# StmPulse-V2-inprogress.net
KiCad netlist of a schematic drawn in EAGLE
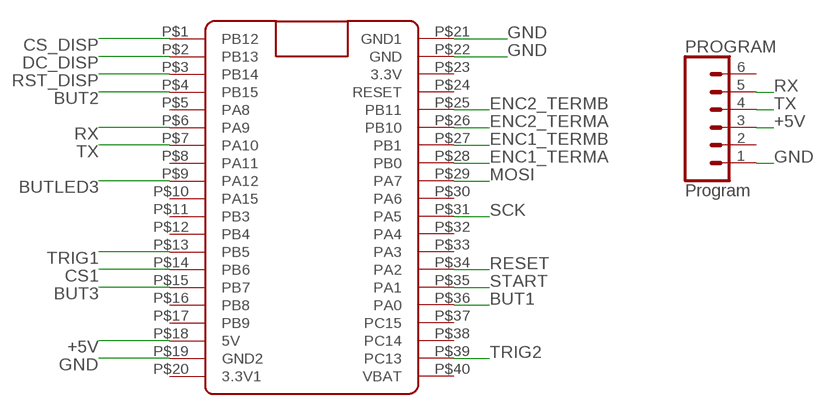
[diagram p0: schematic, sheet 1]
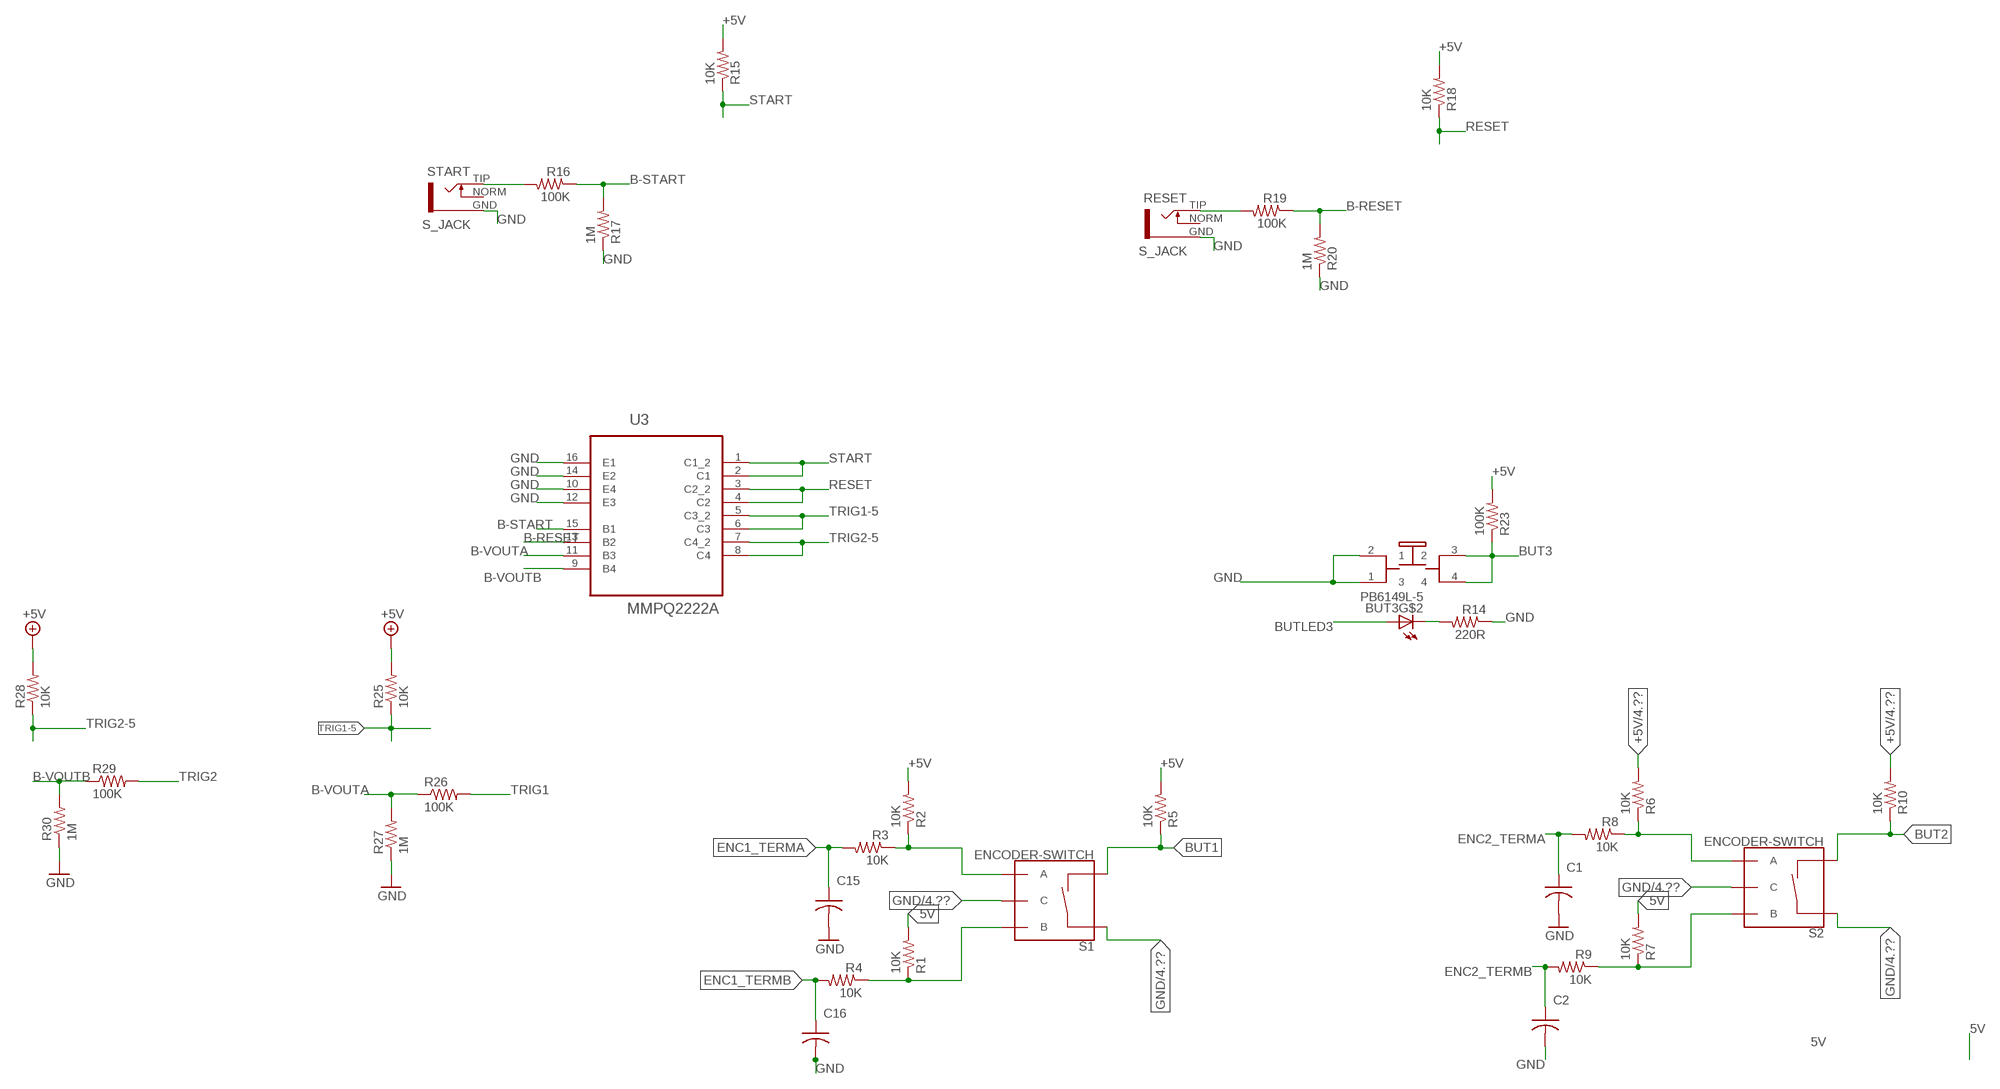
[diagram p1: schematic, sheet 2]
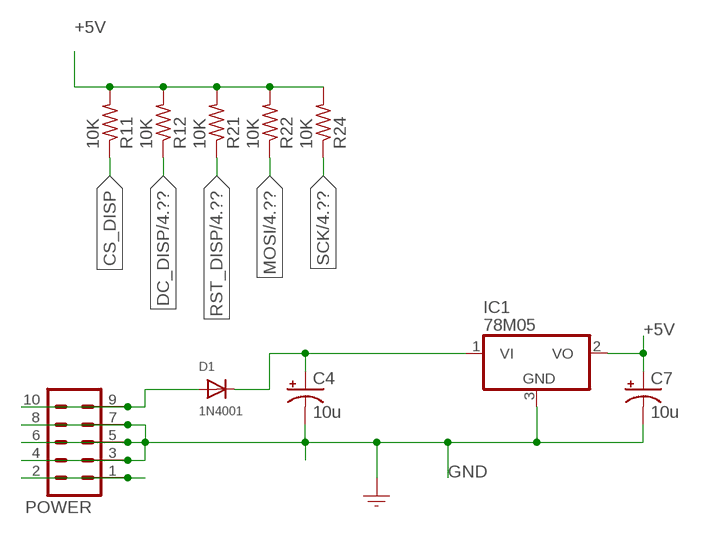
[diagram p2: schematic, sheet 3]
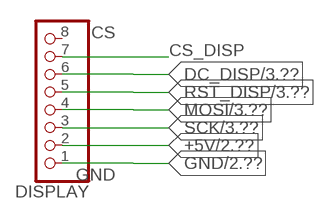
[diagram p3: schematic, sheet 4]
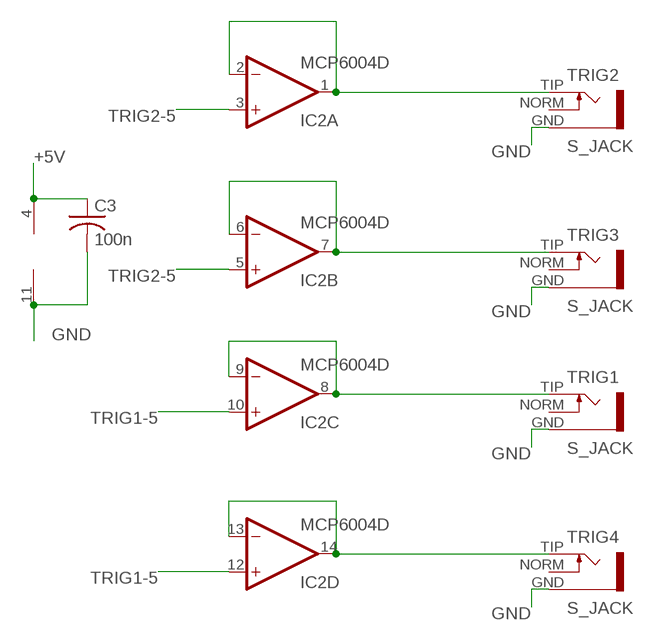
[diagram p4: schematic, sheet 5]
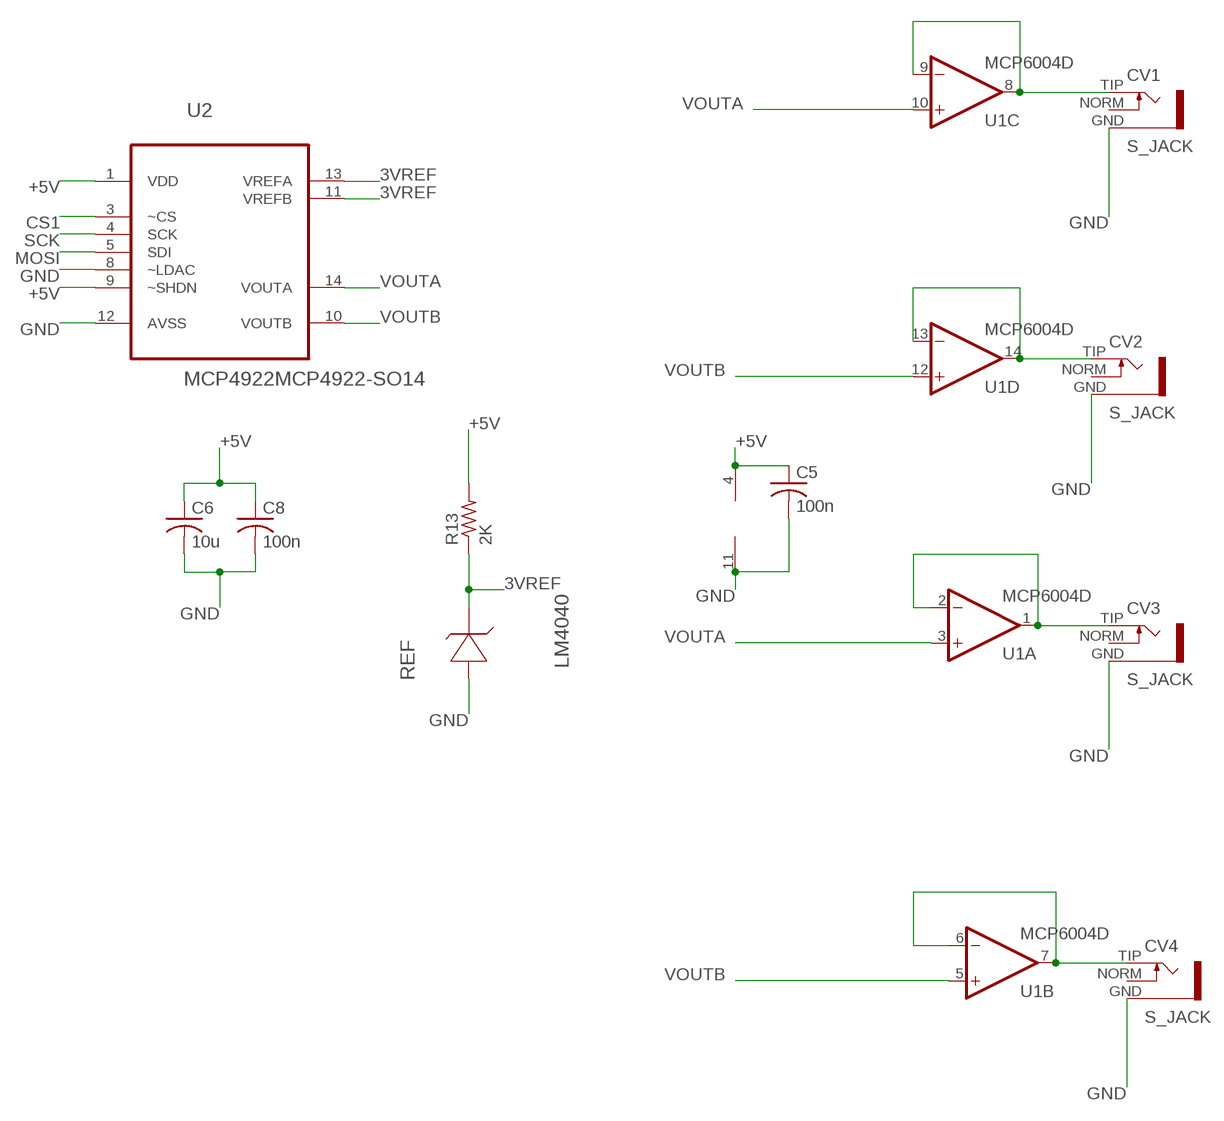
[diagram p5: schematic, sheet 6]

(export (version "E")
  (design (tool "Eeschema 10.0.6"))
  (components
    (comp (ref "BUT3")
      (value "PB6149L-5")
      (footprint "eagle-import:PB6149L")
      (libsource (lib "eagle-import") (part "PB6149L-5"))
    )
    (comp (ref "C1")
      (value "10nF")
      (footprint "eagle-import:C0805")
      (libsource (lib "eagle-import") (part "C-USC0805"))
    )
    (comp (ref "C2")
      (value "10nF")
      (footprint "eagle-import:C0805")
      (libsource (lib "eagle-import") (part "C-USC0805"))
    )
    (comp (ref "C15")
      (value "10nF")
      (footprint "eagle-import:C0805")
      (libsource (lib "eagle-import") (part "C-USC0805"))
    )
    (comp (ref "C16")
      (value "10nF")
      (footprint "eagle-import:C0805")
      (libsource (lib "eagle-import") (part "C-USC0805"))
    )
    (comp (ref "R1")
      (value "10K")
      (footprint "eagle-import:R0805")
      (libsource (lib "eagle-import") (part "R-US_R0805"))
    )
    (comp (ref "R2")
      (value "10K")
      (footprint "eagle-import:R0805")
      (libsource (lib "eagle-import") (part "R-US_R0805"))
    )
    (comp (ref "R3")
      (value "10K")
      (footprint "eagle-import:R0805")
      (libsource (lib "eagle-import") (part "R-US_R0805"))
    )
    (comp (ref "R4")
      (value "10K")
      (footprint "eagle-import:R0805")
      (libsource (lib "eagle-import") (part "R-US_R0805"))
    )
    (comp (ref "R5")
      (value "10K")
      (footprint "eagle-import:R0805")
      (libsource (lib "eagle-import") (part "R-US_R0805"))
    )
    (comp (ref "R6")
      (value "10K")
      (footprint "eagle-import:R0805")
      (libsource (lib "eagle-import") (part "R-US_R0805"))
    )
    (comp (ref "R7")
      (value "10K")
      (footprint "eagle-import:R0805")
      (libsource (lib "eagle-import") (part "R-US_R0805"))
    )
    (comp (ref "R8")
      (value "10K")
      (footprint "eagle-import:R0805")
      (libsource (lib "eagle-import") (part "R-US_R0805"))
    )
    (comp (ref "R9")
      (value "10K")
      (footprint "eagle-import:R0805")
      (libsource (lib "eagle-import") (part "R-US_R0805"))
    )
    (comp (ref "R10")
      (value "10K")
      (footprint "eagle-import:R0805")
      (libsource (lib "eagle-import") (part "R-US_R0805"))
    )
    (comp (ref "R14")
      (value "220R")
      (footprint "eagle-import:R0805")
      (libsource (lib "eagle-import") (part "R-US_R0805"))
    )
    (comp (ref "R15")
      (value "10K")
      (footprint "eagle-import:R0805")
      (libsource (lib "eagle-import") (part "R-US_R0805"))
    )
    (comp (ref "R16")
      (value "100K")
      (footprint "eagle-import:R0805")
      (libsource (lib "eagle-import") (part "R-US_R0805"))
    )
    (comp (ref "R17")
      (value "1M")
      (footprint "eagle-import:R0805")
      (libsource (lib "eagle-import") (part "R-US_R0805"))
    )
    (comp (ref "R18")
      (value "10K")
      (footprint "eagle-import:R0805")
      (libsource (lib "eagle-import") (part "R-US_R0805"))
    )
    (comp (ref "R19")
      (value "100K")
      (footprint "eagle-import:R0805")
      (libsource (lib "eagle-import") (part "R-US_R0805"))
    )
    (comp (ref "R20")
      (value "1M")
      (footprint "eagle-import:R0805")
      (libsource (lib "eagle-import") (part "R-US_R0805"))
    )
    (comp (ref "R23")
      (value "100K")
      (footprint "eagle-import:R0805")
      (libsource (lib "eagle-import") (part "R-US_R0805"))
    )
    (comp (ref "R25")
      (value "10K")
      (footprint "eagle-import:R0805")
      (libsource (lib "eagle-import") (part "R-US_R0805"))
    )
    (comp (ref "R26")
      (value "100K")
      (footprint "eagle-import:R0805")
      (libsource (lib "eagle-import") (part "R-US_R0805"))
    )
    (comp (ref "R27")
      (value "1M")
      (footprint "eagle-import:R0805")
      (libsource (lib "eagle-import") (part "R-US_R0805"))
    )
    (comp (ref "R28")
      (value "10K")
      (footprint "eagle-import:R0805")
      (libsource (lib "eagle-import") (part "R-US_R0805"))
    )
    (comp (ref "R29")
      (value "100K")
      (footprint "eagle-import:R0805")
      (libsource (lib "eagle-import") (part "R-US_R0805"))
    )
    (comp (ref "R30")
      (value "1M")
      (footprint "eagle-import:R0805")
      (libsource (lib "eagle-import") (part "R-US_R0805"))
    )
    (comp (ref "RESET")
      (value "S_JACK")
      (footprint "eagle-import:S_JACK")
      (libsource (lib "eagle-import") (part "S_JACK"))
    )
    (comp (ref "S1")
      (value "ENCODER-SWITCH")
      (footprint "eagle-import:ROTARY_ENC_PLAIN")
      (libsource (lib "eagle-import") (part "ENCODER-SWITCH"))
    )
    (comp (ref "S2")
      (value "ENCODER-SWITCH")
      (footprint "eagle-import:ROTARY_ENC_PLAIN")
      (libsource (lib "eagle-import") (part "ENCODER-SWITCH"))
    )
    (comp (ref "START")
      (value "S_JACK")
      (footprint "eagle-import:S_JACK")
      (libsource (lib "eagle-import") (part "S_JACK"))
    )
    (comp (ref "U3")
      (value "MMPQ2222A")
      (footprint "eagle-import:SOIC127P600X175-16N")
      (libsource (lib "eagle-import") (part "MMPQ2222A"))
    )
    (comp (ref "DISPLAY")
      (value "MICROBUILDER_HEADER-1X8ROUND")
      (footprint "eagle-import:MICROBUILDER_1X08_ROUND")
      (libsource (lib "eagle-import") (part "MICROBUILDER_HEADER-1X8ROUND"))
    )
    (comp (ref "PROGRAM")
      (value "Program")
      (footprint "eagle-import:1X06")
      (libsource (lib "eagle-import") (part "CONN_06SILK_FEMALE_PTH"))
    )
    (comp (ref "U$1")
      (value "Blue Pill")
      (footprint "eagle-import:BLUE_PILL")
      (libsource (lib "eagle-import") (part "BLUE_PILL"))
    )
    (comp (ref "C3")
      (value "100n")
      (footprint "eagle-import:C0805K")
      (libsource (lib "eagle-import") (part "C-USC0805K"))
    )
    (comp (ref "IC2")
      (value "MCP6004D")
      (footprint "eagle-import:SO14")
      (libsource (lib "eagle-import") (part "MCP6004D"))
    )
    (comp (ref "TRIG1")
      (value "S_JACK")
      (footprint "eagle-import:S_JACK")
      (libsource (lib "eagle-import") (part "S_JACK"))
    )
    (comp (ref "TRIG2")
      (value "S_JACK")
      (footprint "eagle-import:S_JACK")
      (libsource (lib "eagle-import") (part "S_JACK"))
    )
    (comp (ref "TRIG3")
      (value "S_JACK")
      (footprint "eagle-import:S_JACK")
      (libsource (lib "eagle-import") (part "S_JACK"))
    )
    (comp (ref "TRIG4")
      (value "S_JACK")
      (footprint "eagle-import:S_JACK")
      (libsource (lib "eagle-import") (part "S_JACK"))
    )
    (comp (ref "C4")
      (value "10u")
      (footprint "eagle-import:153CLV-0505")
      (libsource (lib "eagle-import") (part "CAPACITOR_POL-US153CLV-0505"))
    )
    (comp (ref "C7")
      (value "10u")
      (footprint "eagle-import:153CLV-0505")
      (libsource (lib "eagle-import") (part "CAPACITOR_POL-US153CLV-0505"))
    )
    (comp (ref "D1")
      (value "1N4001")
      (footprint "eagle-import:SMADIODE")
      (libsource (lib "eagle-import") (part "DIODESMA"))
    )
    (comp (ref "IC1")
      (value "78M05")
      (footprint "eagle-import:TO252")
      (libsource (lib "eagle-import") (part "VOLTAGE_REG_POSDT05"))
    )
    (comp (ref "POWER")
      (value "CONN_05X2SHD_SMD")
      (footprint "eagle-import:2X5-SHROUDED_SMD")
      (fields (field (name "RS-PART") "828-1783"))
      (libsource (lib "eagle-import") (part "CONN_05X2SHD_SMD"))
    )
    (comp (ref "R11")
      (value "10K")
      (footprint "eagle-import:R0805")
      (libsource (lib "eagle-import") (part "R-US_R0805"))
    )
    (comp (ref "R12")
      (value "10K")
      (footprint "eagle-import:R0805")
      (libsource (lib "eagle-import") (part "R-US_R0805"))
    )
    (comp (ref "R21")
      (value "10K")
      (footprint "eagle-import:R0805")
      (libsource (lib "eagle-import") (part "R-US_R0805"))
    )
    (comp (ref "R22")
      (value "10K")
      (footprint "eagle-import:R0805")
      (libsource (lib "eagle-import") (part "R-US_R0805"))
    )
    (comp (ref "R24")
      (value "10K")
      (footprint "eagle-import:R0805")
      (libsource (lib "eagle-import") (part "R-US_R0805"))
    )
    (comp (ref "C5")
      (value "100n")
      (footprint "eagle-import:C0805K")
      (libsource (lib "eagle-import") (part "C-USC0805K"))
    )
    (comp (ref "C6")
      (value "10u")
      (footprint "eagle-import:C0805K")
      (libsource (lib "eagle-import") (part "C-USC0805K"))
    )
    (comp (ref "C8")
      (value "100n")
      (footprint "eagle-import:C0805K")
      (libsource (lib "eagle-import") (part "C-USC0805K"))
    )
    (comp (ref "CV1")
      (value "S_JACK")
      (footprint "eagle-import:S_JACK")
      (libsource (lib "eagle-import") (part "S_JACK"))
    )
    (comp (ref "CV2")
      (value "S_JACK")
      (footprint "eagle-import:S_JACK")
      (libsource (lib "eagle-import") (part "S_JACK"))
    )
    (comp (ref "CV3")
      (value "S_JACK")
      (footprint "eagle-import:S_JACK")
      (libsource (lib "eagle-import") (part "S_JACK"))
    )
    (comp (ref "CV4")
      (value "S_JACK")
      (footprint "eagle-import:S_JACK")
      (libsource (lib "eagle-import") (part "S_JACK"))
    )
    (comp (ref "R13")
      (value "2K")
      (footprint "eagle-import:R0805")
      (libsource (lib "eagle-import") (part "R-US_R0805"))
    )
    (comp (ref "REF")
      (value "LM4040")
      (footprint "eagle-import:SOT95P237X112-3N")
      (fields
        (field (name "MPN") "LM4040A50IDBZT")
        (field (name "MPN_1") "LM4040A30IDBZT")
        (field (name "RS-PART") "809-6343")
      )
      (libsource (lib "eagle-import") (part "LM4040A30IDBZT"))
    )
    (comp (ref "U1")
      (value "MCP6004D")
      (footprint "eagle-import:SO14")
      (fields (field (name "RS-PART") "628-3481 (10)"))
      (libsource (lib "eagle-import") (part "MCP6004D"))
    )
    (comp (ref "U2")
      (value "MCP4922MCP4922-SO14")
      (footprint "eagle-import:SO14")
      (fields (field (name "RS-PART") "402-910 "))
      (libsource (lib "eagle-import") (part "MCP4922MCP4922-SO14"))
    )
  )
  (nets
    (net (code "1") (name "+5V") (class "Default")
      (node (ref "C3") (pin "1") (pinfunction "1_1") (pintype "passive"))
      (node (ref "C5") (pin "1") (pinfunction "1_1") (pintype "passive"))
      (node (ref "C6") (pin "1") (pinfunction "1_1") (pintype "passive"))
      (node (ref "C7") (pin "+") (pinfunction "+_+") (pintype "passive"))
      (node (ref "C8") (pin "1") (pinfunction "1_1") (pintype "passive"))
      (node (ref "DISPLAY") (pin "2") (pinfunction "2_2") (pintype "passive"))
      (node (ref "IC1") (pin "2") (pinfunction "VO_2") (pintype "passive"))
      (node (ref "IC2") (pin "4") (pinfunction "V+_4") (pintype "power_in"))
      (node (ref "PROGRAM") (pin "3") (pinfunction "3_3") (pintype "passive"))
      (node (ref "R10") (pin "2") (pinfunction "2_2") (pintype "passive"))
      (node (ref "R11") (pin "2") (pinfunction "2_2") (pintype "passive"))
      (node (ref "R12") (pin "2") (pinfunction "2_2") (pintype "passive"))
      (node (ref "R13") (pin "2") (pinfunction "2_2") (pintype "passive"))
      (node (ref "R15") (pin "2") (pinfunction "2_2") (pintype "passive"))
      (node (ref "R18") (pin "2") (pinfunction "2_2") (pintype "passive"))
      (node (ref "R2") (pin "2") (pinfunction "2_2") (pintype "passive"))
      (node (ref "R21") (pin "2") (pinfunction "2_2") (pintype "passive"))
      (node (ref "R22") (pin "2") (pinfunction "2_2") (pintype "passive"))
      (node (ref "R23") (pin "2") (pinfunction "2_2") (pintype "passive"))
      (node (ref "R24") (pin "2") (pinfunction "2_2") (pintype "passive"))
      (node (ref "R25") (pin "2") (pinfunction "2_2") (pintype "passive"))
      (node (ref "R28") (pin "2") (pinfunction "2_2") (pintype "passive"))
      (node (ref "R5") (pin "2") (pinfunction "2_2") (pintype "passive"))
      (node (ref "R6") (pin "2") (pinfunction "2_2") (pintype "passive"))
      (node (ref "U$1") (pin "P$18") (pinfunction "5V_P$18") (pintype "bidirectional"))
      (node (ref "U1") (pin "4") (pinfunction "V+_4") (pintype "power_in"))
      (node (ref "U2") (pin "1") (pinfunction "VDD_1") (pintype "power_in"))
      (node (ref "U2") (pin "9") (pinfunction "~{SHDN}_9") (pintype "bidirectional"))
    )
    (net (code "2") (name "3VREF") (class "Default")
      (node (ref "R13") (pin "1") (pinfunction "1_1") (pintype "passive"))
      (node (ref "REF") (pin "1") (pinfunction "CATHODE_1") (pintype "output"))
      (node (ref "U2") (pin "11") (pinfunction "VREFB_11") (pintype "bidirectional"))
      (node (ref "U2") (pin "13") (pinfunction "VREFA_13") (pintype "input"))
    )
    (net (code "3") (name "5V") (class "Default")
      (node (ref "R1") (pin "2") (pinfunction "2_2") (pintype "passive"))
      (node (ref "R7") (pin "2") (pinfunction "2_2") (pintype "passive"))
    )
    (net (code "4") (name "B-RESET") (class "Default")
      (node (ref "R19") (pin "1") (pinfunction "1_1") (pintype "passive"))
      (node (ref "R20") (pin "2") (pinfunction "2_2") (pintype "passive"))
      (node (ref "U3") (pin "13") (pinfunction "B2_13") (pintype "passive"))
    )
    (net (code "5") (name "B-START") (class "Default")
      (node (ref "R16") (pin "1") (pinfunction "1_1") (pintype "passive"))
      (node (ref "R17") (pin "2") (pinfunction "2_2") (pintype "passive"))
      (node (ref "U3") (pin "15") (pinfunction "B1_15") (pintype "passive"))
    )
    (net (code "6") (name "B-VOUTA") (class "Default")
      (node (ref "R26") (pin "1") (pinfunction "1_1") (pintype "passive"))
      (node (ref "R27") (pin "2") (pinfunction "2_2") (pintype "passive"))
      (node (ref "U3") (pin "11") (pinfunction "B3_11") (pintype "passive"))
    )
    (net (code "7") (name "B-VOUTB") (class "Default")
      (node (ref "R29") (pin "1") (pinfunction "1_1") (pintype "passive"))
      (node (ref "R30") (pin "2") (pinfunction "2_2") (pintype "passive"))
      (node (ref "U3") (pin "9") (pinfunction "B4_9") (pintype "passive"))
    )
    (net (code "8") (name "BUT1") (class "Default")
      (node (ref "R5") (pin "1") (pinfunction "1_1") (pintype "passive"))
      (node (ref "S1") (pin "SW-") (pinfunction "SW-_SW-") (pintype "bidirectional"))
      (node (ref "U$1") (pin "P$36") (pinfunction "PA0_P$36") (pintype "bidirectional"))
    )
    (net (code "9") (name "BUT2") (class "Default")
      (node (ref "R10") (pin "1") (pinfunction "1_1") (pintype "passive"))
      (node (ref "S2") (pin "SW-") (pinfunction "SW-_SW-") (pintype "bidirectional"))
      (node (ref "U$1") (pin "P$4") (pinfunction "PB15_P$4") (pintype "bidirectional"))
    )
    (net (code "10") (name "BUT3") (class "Default")
      (node (ref "BUT3") (pin "3") (pinfunction "2_3") (pintype "bidirectional"))
      (node (ref "BUT3") (pin "4") (pinfunction "4_4") (pintype "bidirectional"))
      (node (ref "R23") (pin "1") (pinfunction "1_1") (pintype "passive"))
      (node (ref "U$1") (pin "P$15") (pinfunction "PB7_P$15") (pintype "bidirectional"))
    )
    (net (code "11") (name "BUTLED3") (class "Default")
      (node (ref "BUT3") (pin "A") (pinfunction "A_A") (pintype "passive"))
      (node (ref "U$1") (pin "P$9") (pinfunction "PA12_P$9") (pintype "bidirectional"))
    )
    (net (code "12") (name "CS1") (class "Default")
      (node (ref "U$1") (pin "P$14") (pinfunction "PB6_P$14") (pintype "bidirectional"))
      (node (ref "U2") (pin "3") (pinfunction "~{CS}_3") (pintype "input"))
    )
    (net (code "13") (name "CS_DISP") (class "Default")
      (node (ref "DISPLAY") (pin "7") (pinfunction "7_7") (pintype "passive"))
      (node (ref "R11") (pin "1") (pinfunction "1_1") (pintype "passive"))
      (node (ref "U$1") (pin "P$1") (pinfunction "PB12_P$1") (pintype "bidirectional"))
    )
    (net (code "14") (name "DC_DISP") (class "Default")
      (node (ref "DISPLAY") (pin "6") (pinfunction "6_6") (pintype "passive"))
      (node (ref "R12") (pin "1") (pinfunction "1_1") (pintype "passive"))
      (node (ref "U$1") (pin "P$2") (pinfunction "PB13_P$2") (pintype "bidirectional"))
    )
    (net (code "15") (name "ENC1_TERMA") (class "Default")
      (node (ref "C15") (pin "1") (pinfunction "1_1") (pintype "passive"))
      (node (ref "R3") (pin "2") (pinfunction "2_2") (pintype "passive"))
      (node (ref "U$1") (pin "P$28") (pinfunction "PB0_P$28") (pintype "bidirectional"))
    )
    (net (code "16") (name "ENC1_TERMB") (class "Default")
      (node (ref "C16") (pin "1") (pinfunction "1_1") (pintype "passive"))
      (node (ref "R4") (pin "2") (pinfunction "2_2") (pintype "passive"))
      (node (ref "U$1") (pin "P$27") (pinfunction "PB1_P$27") (pintype "bidirectional"))
    )
    (net (code "17") (name "ENC2_TERMA") (class "Default")
      (node (ref "C1") (pin "1") (pinfunction "1_1") (pintype "passive"))
      (node (ref "R8") (pin "2") (pinfunction "2_2") (pintype "passive"))
      (node (ref "U$1") (pin "P$26") (pinfunction "PB10_P$26") (pintype "bidirectional"))
    )
    (net (code "18") (name "ENC2_TERMB") (class "Default")
      (node (ref "C2") (pin "1") (pinfunction "1_1") (pintype "passive"))
      (node (ref "R9") (pin "2") (pinfunction "2_2") (pintype "passive"))
      (node (ref "U$1") (pin "P$25") (pinfunction "PB11_P$25") (pintype "bidirectional"))
    )
    (net (code "19") (name "GND") (class "Default")
      (node (ref "BUT3") (pin "1") (pinfunction "3_1") (pintype "bidirectional"))
      (node (ref "BUT3") (pin "2") (pinfunction "1_2") (pintype "bidirectional"))
      (node (ref "C1") (pin "2") (pinfunction "2_2") (pintype "passive"))
      (node (ref "C15") (pin "2") (pinfunction "2_2") (pintype "passive"))
      (node (ref "C16") (pin "2") (pinfunction "2_2") (pintype "passive"))
      (node (ref "C2") (pin "2") (pinfunction "2_2") (pintype "passive"))
      (node (ref "C3") (pin "2") (pinfunction "2_2") (pintype "passive"))
      (node (ref "C4") (pin "-") (pinfunction "-_-") (pintype "passive"))
      (node (ref "C5") (pin "2") (pinfunction "2_2") (pintype "passive"))
      (node (ref "C6") (pin "2") (pinfunction "2_2") (pintype "passive"))
      (node (ref "C7") (pin "-") (pinfunction "-_-") (pintype "passive"))
      (node (ref "C8") (pin "2") (pinfunction "2_2") (pintype "passive"))
      (node (ref "CV1") (pin "GND") (pinfunction "GND_GND") (pintype "passive"))
      (node (ref "CV2") (pin "GND") (pinfunction "GND_GND") (pintype "passive"))
      (node (ref "CV3") (pin "GND") (pinfunction "GND_GND") (pintype "passive"))
      (node (ref "CV4") (pin "GND") (pinfunction "GND_GND") (pintype "passive"))
      (node (ref "DISPLAY") (pin "1") (pinfunction "1_1") (pintype "passive"))
      (node (ref "IC1") (pin "3") (pinfunction "GND_3") (pintype "passive"))
      (node (ref "IC2") (pin "11") (pinfunction "V-_11") (pintype "power_in"))
      (node (ref "POWER") (pin "3") (pinfunction "3_3") (pintype "passive"))
      (node (ref "POWER") (pin "4") (pinfunction "4_4") (pintype "passive"))
      (node (ref "POWER") (pin "5") (pinfunction "5_5") (pintype "passive"))
      (node (ref "POWER") (pin "6") (pinfunction "6_6") (pintype "passive"))
      (node (ref "POWER") (pin "7") (pinfunction "7_7") (pintype "passive"))
      (node (ref "POWER") (pin "8") (pinfunction "8_8") (pintype "passive"))
      (node (ref "PROGRAM") (pin "1") (pinfunction "1_1") (pintype "passive"))
      (node (ref "R14") (pin "1") (pinfunction "1_1") (pintype "passive"))
      (node (ref "R17") (pin "1") (pinfunction "1_1") (pintype "passive"))
      (node (ref "R20") (pin "1") (pinfunction "1_1") (pintype "passive"))
      (node (ref "R27") (pin "1") (pinfunction "1_1") (pintype "passive"))
      (node (ref "R30") (pin "1") (pinfunction "1_1") (pintype "passive"))
      (node (ref "REF") (pin "2") (pinfunction "ANODE_2") (pintype "input"))
      (node (ref "RESET") (pin "GND") (pinfunction "GND_GND") (pintype "passive"))
      (node (ref "S1") (pin "C") (pinfunction "C_C") (pintype "bidirectional"))
      (node (ref "S1") (pin "SW+") (pinfunction "SW+_SW+") (pintype "bidirectional"))
      (node (ref "S2") (pin "C") (pinfunction "C_C") (pintype "bidirectional"))
      (node (ref "S2") (pin "SW+") (pinfunction "SW+_SW+") (pintype "bidirectional"))
      (node (ref "START") (pin "GND") (pinfunction "GND_GND") (pintype "passive"))
      (node (ref "TRIG1") (pin "GND") (pinfunction "GND_GND") (pintype "passive"))
      (node (ref "TRIG2") (pin "GND") (pinfunction "GND_GND") (pintype "passive"))
      (node (ref "TRIG3") (pin "GND") (pinfunction "GND_GND") (pintype "passive"))
      (node (ref "TRIG4") (pin "GND") (pinfunction "GND_GND") (pintype "passive"))
      (node (ref "U$1") (pin "P$19") (pinfunction "GND2_P$19") (pintype "bidirectional"))
      (node (ref "U$1") (pin "P$21") (pinfunction "GND1_P$21") (pintype "power_in"))
      (node (ref "U$1") (pin "P$22") (pinfunction "GND_P$22") (pintype "bidirectional"))
      (node (ref "U1") (pin "11") (pinfunction "V-_11") (pintype "power_in"))
      (node (ref "U2") (pin "12") (pinfunction "AVSS_12") (pintype "passive"))
      (node (ref "U2") (pin "8") (pinfunction "~{LDAC}_8") (pintype "input"))
      (node (ref "U3") (pin "10") (pinfunction "E4_10") (pintype "passive"))
      (node (ref "U3") (pin "12") (pinfunction "E3_12") (pintype "passive"))
      (node (ref "U3") (pin "14") (pinfunction "E2_14") (pintype "passive"))
      (node (ref "U3") (pin "16") (pinfunction "E1_16") (pintype "passive"))
    )
    (net (code "20") (name "MOSI") (class "Default")
      (node (ref "DISPLAY") (pin "4") (pinfunction "4_4") (pintype "passive"))
      (node (ref "R22") (pin "1") (pinfunction "1_1") (pintype "passive"))
      (node (ref "U$1") (pin "P$29") (pinfunction "PA7_P$29") (pintype "bidirectional"))
      (node (ref "U2") (pin "5") (pinfunction "SDI_5") (pintype "input"))
    )
    (net (code "21") (name "Net-(BUT3B-C)") (class "Default")
      (node (ref "BUT3") (pin "K") (pinfunction "C_K") (pintype "passive"))
      (node (ref "R14") (pin "2") (pinfunction "2_2") (pintype "passive"))
    )
    (net (code "22") (name "Net-(D1-PadA)") (class "Default")
      (node (ref "D1") (pin "A") (pinfunction "A_A") (pintype "passive"))
      (node (ref "POWER") (pin "10") (pinfunction "10_10") (pintype "passive"))
      (node (ref "POWER") (pin "9") (pinfunction "9_9") (pintype "passive"))
    )
    (net (code "23") (name "Net-(IC1-VI)") (class "Default")
      (node (ref "C4") (pin "+") (pinfunction "+_+") (pintype "passive"))
      (node (ref "D1") (pin "C") (pinfunction "C_C") (pintype "passive"))
      (node (ref "IC1") (pin "1") (pinfunction "VI_1") (pintype "input"))
    )
    (net (code "24") (name "Net-(IC2A--IN)") (class "Default")
      (node (ref "IC2") (pin "1") (pinfunction "OUT_1") (pintype "output"))
      (node (ref "IC2") (pin "2") (pinfunction "-IN_2") (pintype "input"))
      (node (ref "TRIG2") (pin "TIP") (pinfunction "TIP_TIP") (pintype "passive"))
    )
    (net (code "25") (name "Net-(IC2B--IN)") (class "Default")
      (node (ref "IC2") (pin "6") (pinfunction "-IN_6") (pintype "input"))
      (node (ref "IC2") (pin "7") (pinfunction "OUT_7") (pintype "output"))
      (node (ref "TRIG3") (pin "TIP") (pinfunction "TIP_TIP") (pintype "passive"))
    )
    (net (code "26") (name "Net-(IC2C--IN)") (class "Default")
      (node (ref "IC2") (pin "8") (pinfunction "OUT_8") (pintype "output"))
      (node (ref "IC2") (pin "9") (pinfunction "-IN_9") (pintype "input"))
      (node (ref "TRIG1") (pin "TIP") (pinfunction "TIP_TIP") (pintype "passive"))
    )
    (net (code "27") (name "Net-(IC2D--IN)") (class "Default")
      (node (ref "IC2") (pin "13") (pinfunction "-IN_13") (pintype "input"))
      (node (ref "IC2") (pin "14") (pinfunction "OUT_14") (pintype "output"))
      (node (ref "TRIG4") (pin "TIP") (pinfunction "TIP_TIP") (pintype "passive"))
    )
    (net (code "28") (name "Net-(POWER-Pad1)") (class "Default")
      (node (ref "POWER") (pin "1") (pinfunction "1_1") (pintype "passive"))
      (node (ref "POWER") (pin "2") (pinfunction "2_2") (pintype "passive"))
    )
    (net (code "29") (name "Net-(R1-Pad1)") (class "Default")
      (node (ref "R1") (pin "1") (pinfunction "1_1") (pintype "passive"))
      (node (ref "R4") (pin "1") (pinfunction "1_1") (pintype "passive"))
      (node (ref "S1") (pin "B") (pinfunction "B_B") (pintype "bidirectional"))
    )
    (net (code "30") (name "Net-(R2-Pad1)") (class "Default")
      (node (ref "R2") (pin "1") (pinfunction "1_1") (pintype "passive"))
      (node (ref "R3") (pin "1") (pinfunction "1_1") (pintype "passive"))
      (node (ref "S1") (pin "A") (pinfunction "A_A") (pintype "bidirectional"))
    )
    (net (code "31") (name "Net-(R6-Pad1)") (class "Default")
      (node (ref "R6") (pin "1") (pinfunction "1_1") (pintype "passive"))
      (node (ref "R8") (pin "1") (pinfunction "1_1") (pintype "passive"))
      (node (ref "S2") (pin "A") (pinfunction "A_A") (pintype "bidirectional"))
    )
    (net (code "32") (name "Net-(R7-Pad1)") (class "Default")
      (node (ref "R7") (pin "1") (pinfunction "1_1") (pintype "passive"))
      (node (ref "R9") (pin "1") (pinfunction "1_1") (pintype "passive"))
      (node (ref "S2") (pin "B") (pinfunction "B_B") (pintype "bidirectional"))
    )
    (net (code "33") (name "Net-(R16-Pad2)") (class "Default")
      (node (ref "R16") (pin "2") (pinfunction "2_2") (pintype "passive"))
      (node (ref "START") (pin "TIP") (pinfunction "TIP_TIP") (pintype "passive"))
    )
    (net (code "34") (name "Net-(R19-Pad2)") (class "Default")
      (node (ref "R19") (pin "2") (pinfunction "2_2") (pintype "passive"))
      (node (ref "RESET") (pin "TIP") (pinfunction "TIP_TIP") (pintype "passive"))
    )
    (net (code "35") (name "Net-(U1A--IN)") (class "Default")
      (node (ref "CV3") (pin "TIP") (pinfunction "TIP_TIP") (pintype "passive"))
      (node (ref "U1") (pin "1") (pinfunction "OUT_1") (pintype "output"))
      (node (ref "U1") (pin "2") (pinfunction "-IN_2") (pintype "input"))
    )
    (net (code "36") (name "Net-(U1B--IN)") (class "Default")
      (node (ref "CV4") (pin "TIP") (pinfunction "TIP_TIP") (pintype "passive"))
      (node (ref "U1") (pin "6") (pinfunction "-IN_6") (pintype "input"))
      (node (ref "U1") (pin "7") (pinfunction "OUT_7") (pintype "output"))
    )
    (net (code "37") (name "Net-(U1C--IN)") (class "Default")
      (node (ref "CV1") (pin "TIP") (pinfunction "TIP_TIP") (pintype "passive"))
      (node (ref "U1") (pin "8") (pinfunction "OUT_8") (pintype "output"))
      (node (ref "U1") (pin "9") (pinfunction "-IN_9") (pintype "input"))
    )
    (net (code "38") (name "Net-(U1D--IN)") (class "Default")
      (node (ref "CV2") (pin "TIP") (pinfunction "TIP_TIP") (pintype "passive"))
      (node (ref "U1") (pin "13") (pinfunction "-IN_13") (pintype "input"))
      (node (ref "U1") (pin "14") (pinfunction "OUT_14") (pintype "output"))
    )
    (net (code "39") (name "RESET") (class "Default")
      (node (ref "R18") (pin "1") (pinfunction "1_1") (pintype "passive"))
      (node (ref "U$1") (pin "P$34") (pinfunction "PA2_P$34") (pintype "bidirectional"))
      (node (ref "U3") (pin "3") (pinfunction "C2_2_3") (pintype "passive"))
      (node (ref "U3") (pin "4") (pinfunction "C2_4") (pintype "passive"))
    )
    (net (code "40") (name "RST_DISP") (class "Default")
      (node (ref "DISPLAY") (pin "5") (pinfunction "5_5") (pintype "passive"))
      (node (ref "R21") (pin "1") (pinfunction "1_1") (pintype "passive"))
      (node (ref "U$1") (pin "P$3") (pinfunction "PB14_P$3") (pintype "bidirectional"))
    )
    (net (code "41") (name "RX") (class "Default")
      (node (ref "PROGRAM") (pin "5") (pinfunction "5_5") (pintype "passive"))
      (node (ref "U$1") (pin "P$6") (pinfunction "PA9_P$6") (pintype "bidirectional"))
    )
    (net (code "42") (name "SCK") (class "Default")
      (node (ref "DISPLAY") (pin "3") (pinfunction "3_3") (pintype "passive"))
      (node (ref "R24") (pin "1") (pinfunction "1_1") (pintype "passive"))
      (node (ref "U$1") (pin "P$31") (pinfunction "PA5_P$31") (pintype "bidirectional"))
      (node (ref "U2") (pin "4") (pinfunction "SCK_4") (pintype "input"))
    )
    (net (code "43") (name "START") (class "Default")
      (node (ref "R15") (pin "1") (pinfunction "1_1") (pintype "passive"))
      (node (ref "U$1") (pin "P$35") (pinfunction "PA1_P$35") (pintype "bidirectional"))
      (node (ref "U3") (pin "1") (pinfunction "C1_2_1") (pintype "passive"))
      (node (ref "U3") (pin "2") (pinfunction "C1_2") (pintype "passive"))
    )
    (net (code "44") (name "TRIG1") (class "Default")
      (node (ref "R26") (pin "2") (pinfunction "2_2") (pintype "passive"))
      (node (ref "U$1") (pin "P$13") (pinfunction "PB5_P$13") (pintype "bidirectional"))
    )
    (net (code "45") (name "TRIG1-5") (class "Default")
      (node (ref "IC2") (pin "10") (pinfunction "+IN_10") (pintype "input"))
      (node (ref "IC2") (pin "12") (pinfunction "+IN_12") (pintype "input"))
      (node (ref "R25") (pin "1") (pinfunction "1_1") (pintype "passive"))
      (node (ref "U3") (pin "5") (pinfunction "C3_2_5") (pintype "passive"))
      (node (ref "U3") (pin "6") (pinfunction "C3_6") (pintype "passive"))
    )
    (net (code "46") (name "TRIG2") (class "Default")
      (node (ref "R29") (pin "2") (pinfunction "2_2") (pintype "passive"))
      (node (ref "U$1") (pin "P$39") (pinfunction "PC13_P$39") (pintype "bidirectional"))
    )
    (net (code "47") (name "TRIG2-5") (class "Default")
      (node (ref "IC2") (pin "3") (pinfunction "+IN_3") (pintype "input"))
      (node (ref "IC2") (pin "5") (pinfunction "+IN_5") (pintype "input"))
      (node (ref "R28") (pin "1") (pinfunction "1_1") (pintype "passive"))
      (node (ref "U3") (pin "7") (pinfunction "C4_2_7") (pintype "passive"))
      (node (ref "U3") (pin "8") (pinfunction "C4_8") (pintype "passive"))
    )
    (net (code "48") (name "TX") (class "Default")
      (node (ref "PROGRAM") (pin "4") (pinfunction "4_4") (pintype "passive"))
      (node (ref "U$1") (pin "P$7") (pinfunction "PA10_P$7") (pintype "bidirectional"))
    )
    (net (code "49") (name "VOUTA") (class "Default")
      (node (ref "U1") (pin "10") (pinfunction "+IN_10") (pintype "input"))
      (node (ref "U1") (pin "3") (pinfunction "+IN_3") (pintype "input"))
      (node (ref "U2") (pin "14") (pinfunction "VOUTA_14") (pintype "output"))
    )
    (net (code "50") (name "VOUTB") (class "Default")
      (node (ref "U1") (pin "12") (pinfunction "+IN_12") (pintype "input"))
      (node (ref "U1") (pin "5") (pinfunction "+IN_5") (pintype "input"))
      (node (ref "U2") (pin "10") (pinfunction "VOUTB_10") (pintype "output"))
    )
    (net (code "51") (name "unconnected-(CV1-PadNORM)") (class "Default")
      (node (ref "CV1") (pin "NORM") (pinfunction "NORM_NORM") (pintype "passive"))
    )
    (net (code "52") (name "unconnected-(CV2-PadNORM)") (class "Default")
      (node (ref "CV2") (pin "NORM") (pinfunction "NORM_NORM") (pintype "passive"))
    )
    (net (code "53") (name "unconnected-(CV3-PadNORM)") (class "Default")
      (node (ref "CV3") (pin "NORM") (pinfunction "NORM_NORM") (pintype "passive"))
    )
    (net (code "54") (name "unconnected-(CV4-PadNORM)") (class "Default")
      (node (ref "CV4") (pin "NORM") (pinfunction "NORM_NORM") (pintype "passive"))
    )
    (net (code "55") (name "unconnected-(DISPLAY-Pad8)") (class "Default")
      (node (ref "DISPLAY") (pin "8") (pinfunction "8_8") (pintype "passive"))
    )
    (net (code "56") (name "unconnected-(PROGRAM-Pad2)") (class "Default")
      (node (ref "PROGRAM") (pin "2") (pinfunction "2_2") (pintype "passive"))
    )
    (net (code "57") (name "unconnected-(PROGRAM-Pad6)") (class "Default")
      (node (ref "PROGRAM") (pin "6") (pinfunction "6_6") (pintype "passive"))
    )
    (net (code "58") (name "unconnected-(REF-NC-Pad3)") (class "Default")
      (node (ref "REF") (pin "3") (pinfunction "NC_3") (pintype "no_connect"))
    )
    (net (code "59") (name "unconnected-(RESET-PadNORM)") (class "Default")
      (node (ref "RESET") (pin "NORM") (pinfunction "NORM_NORM") (pintype "passive"))
    )
    (net (code "60") (name "unconnected-(START-PadNORM)") (class "Default")
      (node (ref "START") (pin "NORM") (pinfunction "NORM_NORM") (pintype "passive"))
    )
    (net (code "61") (name "unconnected-(TRIG1-PadNORM)") (class "Default")
      (node (ref "TRIG1") (pin "NORM") (pinfunction "NORM_NORM") (pintype "passive"))
    )
    (net (code "62") (name "unconnected-(TRIG2-PadNORM)") (class "Default")
      (node (ref "TRIG2") (pin "NORM") (pinfunction "NORM_NORM") (pintype "passive"))
    )
    (net (code "63") (name "unconnected-(TRIG3-PadNORM)") (class "Default")
      (node (ref "TRIG3") (pin "NORM") (pinfunction "NORM_NORM") (pintype "passive"))
    )
    (net (code "64") (name "unconnected-(TRIG4-PadNORM)") (class "Default")
      (node (ref "TRIG4") (pin "NORM") (pinfunction "NORM_NORM") (pintype "passive"))
    )
    (net (code "65") (name "unconnected-(U$1-3.3V-PadP$23)") (class "Default")
      (node (ref "U$1") (pin "P$23") (pinfunction "3.3V_P$23") (pintype "bidirectional"))
    )
    (net (code "66") (name "unconnected-(U$1-3.3V1-PadP$20)") (class "Default")
      (node (ref "U$1") (pin "P$20") (pinfunction "3.3V1_P$20") (pintype "bidirectional"))
    )
    (net (code "67") (name "unconnected-(U$1-PA3-PadP$33)") (class "Default")
      (node (ref "U$1") (pin "P$33") (pinfunction "PA3_P$33") (pintype "bidirectional"))
    )
    (net (code "68") (name "unconnected-(U$1-PA4-PadP$32)") (class "Default")
      (node (ref "U$1") (pin "P$32") (pinfunction "PA4_P$32") (pintype "bidirectional"))
    )
    (net (code "69") (name "unconnected-(U$1-PA6-PadP$30)") (class "Default")
      (node (ref "U$1") (pin "P$30") (pinfunction "PA6_P$30") (pintype "bidirectional"))
    )
    (net (code "70") (name "unconnected-(U$1-PA8-PadP$5)") (class "Default")
      (node (ref "U$1") (pin "P$5") (pinfunction "PA8_P$5") (pintype "bidirectional"))
    )
    (net (code "71") (name "unconnected-(U$1-PA11-PadP$8)") (class "Default")
      (node (ref "U$1") (pin "P$8") (pinfunction "PA11_P$8") (pintype "bidirectional"))
    )
    (net (code "72") (name "unconnected-(U$1-PA15-PadP$10)") (class "Default")
      (node (ref "U$1") (pin "P$10") (pinfunction "PA15_P$10") (pintype "bidirectional"))
    )
    (net (code "73") (name "unconnected-(U$1-PB3-PadP$11)") (class "Default")
      (node (ref "U$1") (pin "P$11") (pinfunction "PB3_P$11") (pintype "bidirectional"))
    )
    (net (code "74") (name "unconnected-(U$1-PB4-PadP$12)") (class "Default")
      (node (ref "U$1") (pin "P$12") (pinfunction "PB4_P$12") (pintype "bidirectional"))
    )
    (net (code "75") (name "unconnected-(U$1-PB8-PadP$16)") (class "Default")
      (node (ref "U$1") (pin "P$16") (pinfunction "PB8_P$16") (pintype "bidirectional"))
    )
    (net (code "76") (name "unconnected-(U$1-PB9-PadP$17)") (class "Default")
      (node (ref "U$1") (pin "P$17") (pinfunction "PB9_P$17") (pintype "bidirectional"))
    )
    (net (code "77") (name "unconnected-(U$1-PC14-PadP$38)") (class "Default")
      (node (ref "U$1") (pin "P$38") (pinfunction "PC14_P$38") (pintype "bidirectional"))
    )
    (net (code "78") (name "unconnected-(U$1-PC15-PadP$37)") (class "Default")
      (node (ref "U$1") (pin "P$37") (pinfunction "PC15_P$37") (pintype "bidirectional"))
    )
    (net (code "79") (name "unconnected-(U$1-RESET-PadP$24)") (class "Default")
      (node (ref "U$1") (pin "P$24") (pinfunction "RESET_P$24") (pintype "bidirectional"))
    )
    (net (code "80") (name "unconnected-(U$1-VBAT-PadP$40)") (class "Default")
      (node (ref "U$1") (pin "P$40") (pinfunction "VBAT_P$40") (pintype "bidirectional"))
    )
  )
)
